# Deneme_Devresi-08_12_2024-_ematik_-_Kopy.net
KiCad netlist of a schematic drawn in EAGLE
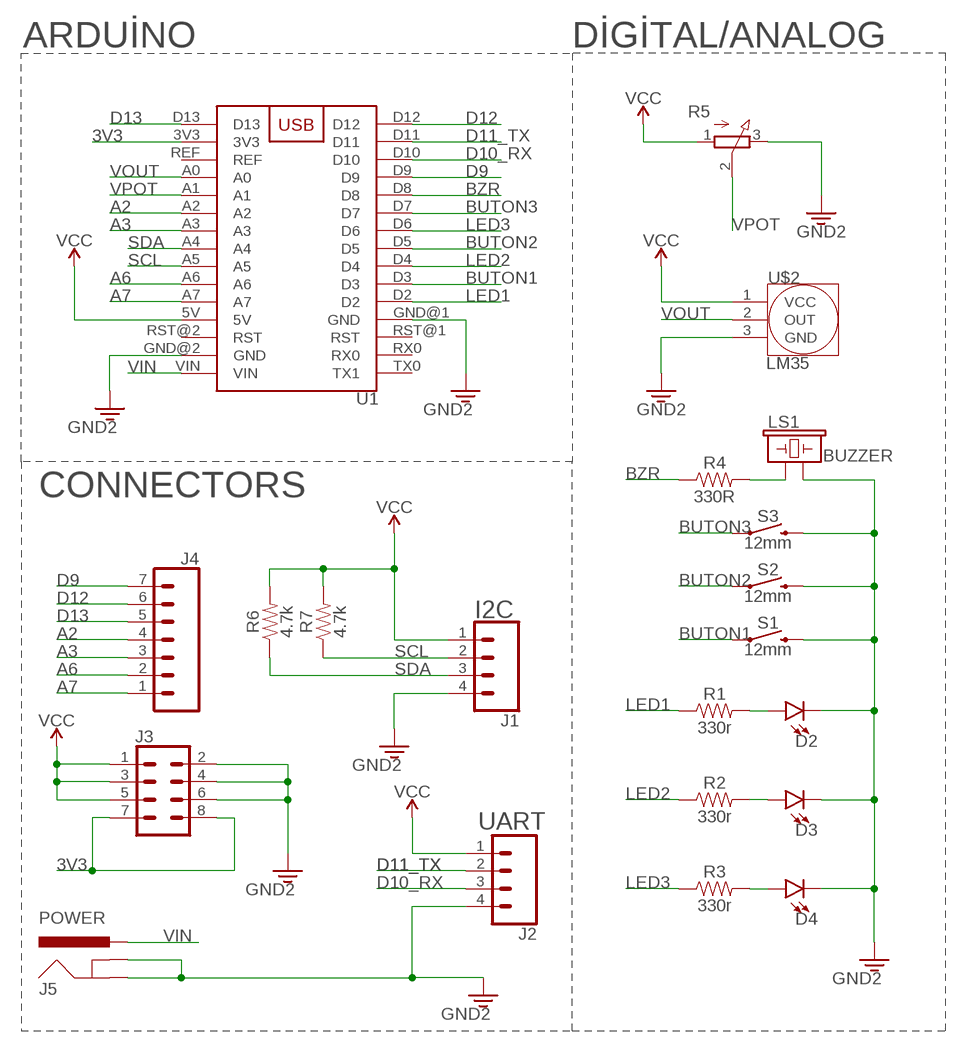
[diagram p0: schematic, sheet 1]

(export (version "E")
  (design (tool "Eeschema 10.0.6"))
  (components
    (comp (ref "D2")
      (value "LED-3MM-NO_SILK")
      (footprint "eagle-import:LED_3MM-NS")
      (libsource (lib "eagle-import") (part "LED-3MM-NO_SILK"))
    )
    (comp (ref "D3")
      (value "LED-3MM-NO_SILK")
      (footprint "eagle-import:LED_3MM-NS")
      (libsource (lib "eagle-import") (part "LED-3MM-NO_SILK"))
    )
    (comp (ref "D4")
      (value "LED-3MM-NO_SILK")
      (footprint "eagle-import:LED_3MM-NS")
      (libsource (lib "eagle-import") (part "LED-3MM-NO_SILK"))
    )
    (comp (ref "J1")
      (value "CONN_04JST-PTH")
      (footprint "eagle-import:JST-4-PTH")
      (libsource (lib "eagle-import") (part "CONN_04JST-PTH"))
    )
    (comp (ref "J2")
      (value "CONN_04JST-PTH")
      (footprint "eagle-import:JST-4-PTH")
      (libsource (lib "eagle-import") (part "CONN_04JST-PTH"))
    )
    (comp (ref "J3")
      (value "CONN_04X2")
      (footprint "eagle-import:2X4")
      (libsource (lib "eagle-import") (part "CONN_04X2"))
    )
    (comp (ref "J4")
      (value "CONN_07NO_SILK")
      (footprint "eagle-import:1X07_NO_SILK")
      (libsource (lib "eagle-import") (part "CONN_07NO_SILK"))
    )
    (comp (ref "J5")
      (value "POWER")
      (footprint "eagle-import:POWER_JACK_PTH_SLOT_NO_OVRHNG_SILK")
      (libsource (lib "eagle-import") (part "POWER_JACKPOWER_JACK_SLOT_NO_SILK_OVRHNG"))
    )
    (comp (ref "LS1")
      (value "BUZZER")
      (footprint "eagle-import:BUZZER-12MM-NS")
      (libsource (lib "eagle-import") (part "BUZZER-PTH_NO_SILK"))
    )
    (comp (ref "R1")
      (value "330r")
      (footprint "eagle-import:AXIAL-0.3")
      (libsource (lib "eagle-import") (part "1KOHM-HORIZ-1/4W-5%"))
    )
    (comp (ref "R2")
      (value "330r")
      (footprint "eagle-import:AXIAL-0.3")
      (libsource (lib "eagle-import") (part "1KOHM-HORIZ-1/4W-5%"))
    )
    (comp (ref "R3")
      (value "330r")
      (footprint "eagle-import:AXIAL-0.3")
      (libsource (lib "eagle-import") (part "1KOHM-HORIZ-1/4W-5%"))
    )
    (comp (ref "R4")
      (value "330R")
      (footprint "eagle-import:AXIAL-0.3")
      (libsource (lib "eagle-import") (part "1KOHM-HORIZ-1/4W-5%"))
    )
    (comp (ref "R5")
      (value "3RP/1610N")
      (footprint "eagle-import:3RP_1610N")
      (libsource (lib "eagle-import") (part "3RP/1610N"))
    )
    (comp (ref "R6")
      (value "4.7k")
      (footprint "eagle-import:AXIAL-0.3")
      (libsource (lib "eagle-import") (part "1KOHM-HORIZ-1/4W-5%"))
    )
    (comp (ref "R7")
      (value "4.7k")
      (footprint "eagle-import:AXIAL-0.3")
      (libsource (lib "eagle-import") (part "1KOHM-HORIZ-1/4W-5%"))
    )
    (comp (ref "S1")
      (value "12mm")
      (footprint "eagle-import:TACTILE_SWITCH_PTH_12MM")
      (libsource (lib "eagle-import") (part "MOMENTARY-SWITCH-SPST-PTH-12MM"))
    )
    (comp (ref "S2")
      (value "12mm")
      (footprint "eagle-import:TACTILE_SWITCH_PTH_12MM")
      (libsource (lib "eagle-import") (part "MOMENTARY-SWITCH-SPST-PTH-12MM"))
    )
    (comp (ref "S3")
      (value "12mm")
      (footprint "eagle-import:TACTILE_SWITCH_PTH_12MM")
      (libsource (lib "eagle-import") (part "MOMENTARY-SWITCH-SPST-PTH-12MM"))
    )
    (comp (ref "U$2")
      (value "LM35")
      (footprint "eagle-import:TO-92")
      (libsource (lib "eagle-import") (part "LM35"))
    )
    (comp (ref "U1")
      (value "ARDUINO_NANO")
      (footprint "eagle-import:ARDUINO_NANO")
      (libsource (lib "eagle-import") (part "ARDUINO_NANO"))
    )
  )
  (nets
    (net (code "1") (name "/3V3") (class "Default")
      (node (ref "J3") (pin "7") (pinfunction "7_7") (pintype "passive"))
      (node (ref "J3") (pin "8") (pinfunction "8_8") (pintype "passive"))
      (node (ref "U1") (pin "3V3") (pinfunction "3V3_3V3") (pintype "bidirectional"))
    )
    (net (code "2") (name "/A2") (class "Default")
      (node (ref "J4") (pin "4") (pinfunction "4_4") (pintype "passive"))
      (node (ref "U1") (pin "A2") (pinfunction "A2_A2") (pintype "bidirectional"))
    )
    (net (code "3") (name "/A3") (class "Default")
      (node (ref "J4") (pin "3") (pinfunction "3_3") (pintype "passive"))
      (node (ref "U1") (pin "A3") (pinfunction "A3_A3") (pintype "bidirectional"))
    )
    (net (code "4") (name "/A6") (class "Default")
      (node (ref "J4") (pin "2") (pinfunction "2_2") (pintype "passive"))
      (node (ref "U1") (pin "A6") (pinfunction "A6_A6") (pintype "bidirectional"))
    )
    (net (code "5") (name "/A7") (class "Default")
      (node (ref "J4") (pin "1") (pinfunction "1_1") (pintype "passive"))
      (node (ref "U1") (pin "A7") (pinfunction "A7_A7") (pintype "bidirectional"))
    )
    (net (code "6") (name "/BUTON1") (class "Default")
      (node (ref "S1") (pin "1") (pinfunction "1_1") (pintype "passive"))
      (node (ref "U1") (pin "D3") (pinfunction "D3_D3") (pintype "bidirectional"))
    )
    (net (code "7") (name "/BUTON2") (class "Default")
      (node (ref "S2") (pin "1") (pinfunction "1_1") (pintype "passive"))
      (node (ref "U1") (pin "D5") (pinfunction "D5_D5") (pintype "bidirectional"))
    )
    (net (code "8") (name "/BUTON3") (class "Default")
      (node (ref "S3") (pin "1") (pinfunction "1_1") (pintype "passive"))
      (node (ref "U1") (pin "D7") (pinfunction "D7_D7") (pintype "bidirectional"))
    )
    (net (code "9") (name "/BZR") (class "Default")
      (node (ref "R4") (pin "P$1") (pinfunction "1_P$1") (pintype "passive"))
      (node (ref "U1") (pin "D8") (pinfunction "D8_D8") (pintype "bidirectional"))
    )
    (net (code "10") (name "/D9") (class "Default")
      (node (ref "J4") (pin "7") (pinfunction "7_7") (pintype "passive"))
      (node (ref "U1") (pin "D9") (pinfunction "D9_D9") (pintype "bidirectional"))
    )
    (net (code "11") (name "/D10_RX") (class "Default")
      (node (ref "J2") (pin "3") (pinfunction "3_3") (pintype "passive"))
      (node (ref "U1") (pin "D10") (pinfunction "D10_D10") (pintype "bidirectional"))
    )
    (net (code "12") (name "/D11_TX") (class "Default")
      (node (ref "J2") (pin "2") (pinfunction "2_2") (pintype "passive"))
      (node (ref "U1") (pin "D11") (pinfunction "D11_D11") (pintype "bidirectional"))
    )
    (net (code "13") (name "/D12") (class "Default")
      (node (ref "J4") (pin "6") (pinfunction "6_6") (pintype "passive"))
      (node (ref "U1") (pin "D12") (pinfunction "D12_D12") (pintype "bidirectional"))
    )
    (net (code "14") (name "/D13") (class "Default")
      (node (ref "J4") (pin "5") (pinfunction "5_5") (pintype "passive"))
      (node (ref "U1") (pin "D13") (pinfunction "D13_D13") (pintype "bidirectional"))
    )
    (net (code "15") (name "/LED1") (class "Default")
      (node (ref "R1") (pin "P$1") (pinfunction "1_P$1") (pintype "passive"))
      (node (ref "U1") (pin "D2") (pinfunction "D2_D2") (pintype "bidirectional"))
    )
    (net (code "16") (name "/LED2") (class "Default")
      (node (ref "R2") (pin "P$1") (pinfunction "1_P$1") (pintype "passive"))
      (node (ref "U1") (pin "D4") (pinfunction "D4_D4") (pintype "bidirectional"))
    )
    (net (code "17") (name "/LED3") (class "Default")
      (node (ref "R3") (pin "P$1") (pinfunction "1_P$1") (pintype "passive"))
      (node (ref "U1") (pin "D6") (pinfunction "D6_D6") (pintype "bidirectional"))
    )
    (net (code "18") (name "/SCL") (class "Default")
      (node (ref "J1") (pin "2") (pinfunction "2_2") (pintype "passive"))
      (node (ref "R7") (pin "P$1") (pinfunction "1_P$1") (pintype "passive"))
      (node (ref "U1") (pin "A5") (pinfunction "A5_A5") (pintype "bidirectional"))
    )
    (net (code "19") (name "/SDA") (class "Default")
      (node (ref "J1") (pin "3") (pinfunction "3_3") (pintype "passive"))
      (node (ref "R6") (pin "P$1") (pinfunction "1_P$1") (pintype "passive"))
      (node (ref "U1") (pin "A4") (pinfunction "A4_A4") (pintype "bidirectional"))
    )
    (net (code "20") (name "/VIN") (class "Default")
      (node (ref "J5") (pin "PWR") (pinfunction "PWR_PWR") (pintype "bidirectional"))
      (node (ref "U1") (pin "VIN") (pinfunction "VIN_VIN") (pintype "bidirectional"))
    )
    (net (code "21") (name "/VOUT") (class "Default")
      (node (ref "U$2") (pin "2") (pinfunction "OUT_2") (pintype "bidirectional"))
      (node (ref "U1") (pin "A0") (pinfunction "A0_A0") (pintype "bidirectional"))
    )
    (net (code "22") (name "/VPOT") (class "Default")
      (node (ref "R5") (pin "2") (pinfunction "S_2") (pintype "passive"))
      (node (ref "U1") (pin "A1") (pinfunction "A1_A1") (pintype "bidirectional"))
    )
    (net (code "23") (name "GND2") (class "Default")
      (node (ref "D2") (pin "K") (pinfunction "C_K") (pintype "passive"))
      (node (ref "D3") (pin "K") (pinfunction "C_K") (pintype "passive"))
      (node (ref "D4") (pin "K") (pinfunction "C_K") (pintype "passive"))
      (node (ref "J1") (pin "4") (pinfunction "4_4") (pintype "passive"))
      (node (ref "J2") (pin "4") (pinfunction "4_4") (pintype "passive"))
      (node (ref "J3") (pin "2") (pinfunction "2_2") (pintype "passive"))
      (node (ref "J3") (pin "4") (pinfunction "4_4") (pintype "passive"))
      (node (ref "J3") (pin "6") (pinfunction "6_6") (pintype "passive"))
      (node (ref "J5") (pin "GND") (pinfunction "GND_GND") (pintype "bidirectional"))
      (node (ref "J5") (pin "GNDBREAK") (pinfunction "GNDBREAK_GNDBREAK") (pintype "bidirectional"))
      (node (ref "LS1") (pin "-") (pinfunction "2_-") (pintype "passive"))
      (node (ref "R5") (pin "3") (pinfunction "E_3") (pintype "passive"))
      (node (ref "S1") (pin "3") (pinfunction "2_3") (pintype "passive"))
      (node (ref "S2") (pin "3") (pinfunction "2_3") (pintype "passive"))
      (node (ref "S3") (pin "3") (pinfunction "2_3") (pintype "passive"))
      (node (ref "U$2") (pin "3") (pinfunction "GND_3") (pintype "bidirectional"))
      (node (ref "U1") (pin "GND@1") (pinfunction "GND_GND@1") (pintype "bidirectional"))
      (node (ref "U1") (pin "GND@2") (pinfunction "GND_GND@2") (pintype "bidirectional"))
    )
    (net (code "24") (name "Net-(LS1-1)") (class "Default")
      (node (ref "LS1") (pin "+") (pinfunction "1_+") (pintype "passive"))
      (node (ref "R4") (pin "P$2") (pinfunction "2_P$2") (pintype "passive"))
    )
    (net (code "25") (name "Net-(R1-2)") (class "Default")
      (node (ref "D2") (pin "A") (pinfunction "A_A") (pintype "passive"))
      (node (ref "R1") (pin "P$2") (pinfunction "2_P$2") (pintype "passive"))
    )
    (net (code "26") (name "Net-(R2-2)") (class "Default")
      (node (ref "D3") (pin "A") (pinfunction "A_A") (pintype "passive"))
      (node (ref "R2") (pin "P$2") (pinfunction "2_P$2") (pintype "passive"))
    )
    (net (code "27") (name "Net-(R3-2)") (class "Default")
      (node (ref "D4") (pin "A") (pinfunction "A_A") (pintype "passive"))
      (node (ref "R3") (pin "P$2") (pinfunction "2_P$2") (pintype "passive"))
    )
    (net (code "28") (name "VCC") (class "Default")
      (node (ref "J1") (pin "1") (pinfunction "1_1") (pintype "passive"))
      (node (ref "J2") (pin "1") (pinfunction "1_1") (pintype "passive"))
      (node (ref "J3") (pin "1") (pinfunction "1_1") (pintype "passive"))
      (node (ref "J3") (pin "3") (pinfunction "3_3") (pintype "passive"))
      (node (ref "J3") (pin "5") (pinfunction "5_5") (pintype "passive"))
      (node (ref "R5") (pin "1") (pinfunction "A_1") (pintype "passive"))
      (node (ref "R6") (pin "P$2") (pinfunction "2_P$2") (pintype "passive"))
      (node (ref "R7") (pin "P$2") (pinfunction "2_P$2") (pintype "passive"))
      (node (ref "U$2") (pin "1") (pinfunction "VCC_1") (pintype "bidirectional"))
      (node (ref "U1") (pin "5V") (pinfunction "5V_5V") (pintype "bidirectional"))
    )
    (net (code "29") (name "unconnected-(U1-PadREF)") (class "Default")
      (node (ref "U1") (pin "REF") (pinfunction "REF_REF") (pintype "bidirectional"))
    )
    (net (code "30") (name "unconnected-(U1-PadRX0)") (class "Default")
      (node (ref "U1") (pin "RX0") (pinfunction "RX0_RX0") (pintype "bidirectional"))
    )
    (net (code "31") (name "unconnected-(U1-RST-PadRST@1)") (class "Default")
      (node (ref "U1") (pin "RST@1") (pinfunction "RST_RST@1") (pintype "bidirectional"))
    )
    (net (code "32") (name "unconnected-(U1-RST-PadRST@2)") (class "Default")
      (node (ref "U1") (pin "RST@2") (pinfunction "RST_RST@2") (pintype "bidirectional"))
    )
    (net (code "33") (name "unconnected-(U1-TX1-PadTX0)") (class "Default")
      (node (ref "U1") (pin "TX0") (pinfunction "TX1_TX0") (pintype "bidirectional"))
    )
  )
)
